# Power_management.net
KiCad netlist of a schematic drawn in Altium Designer
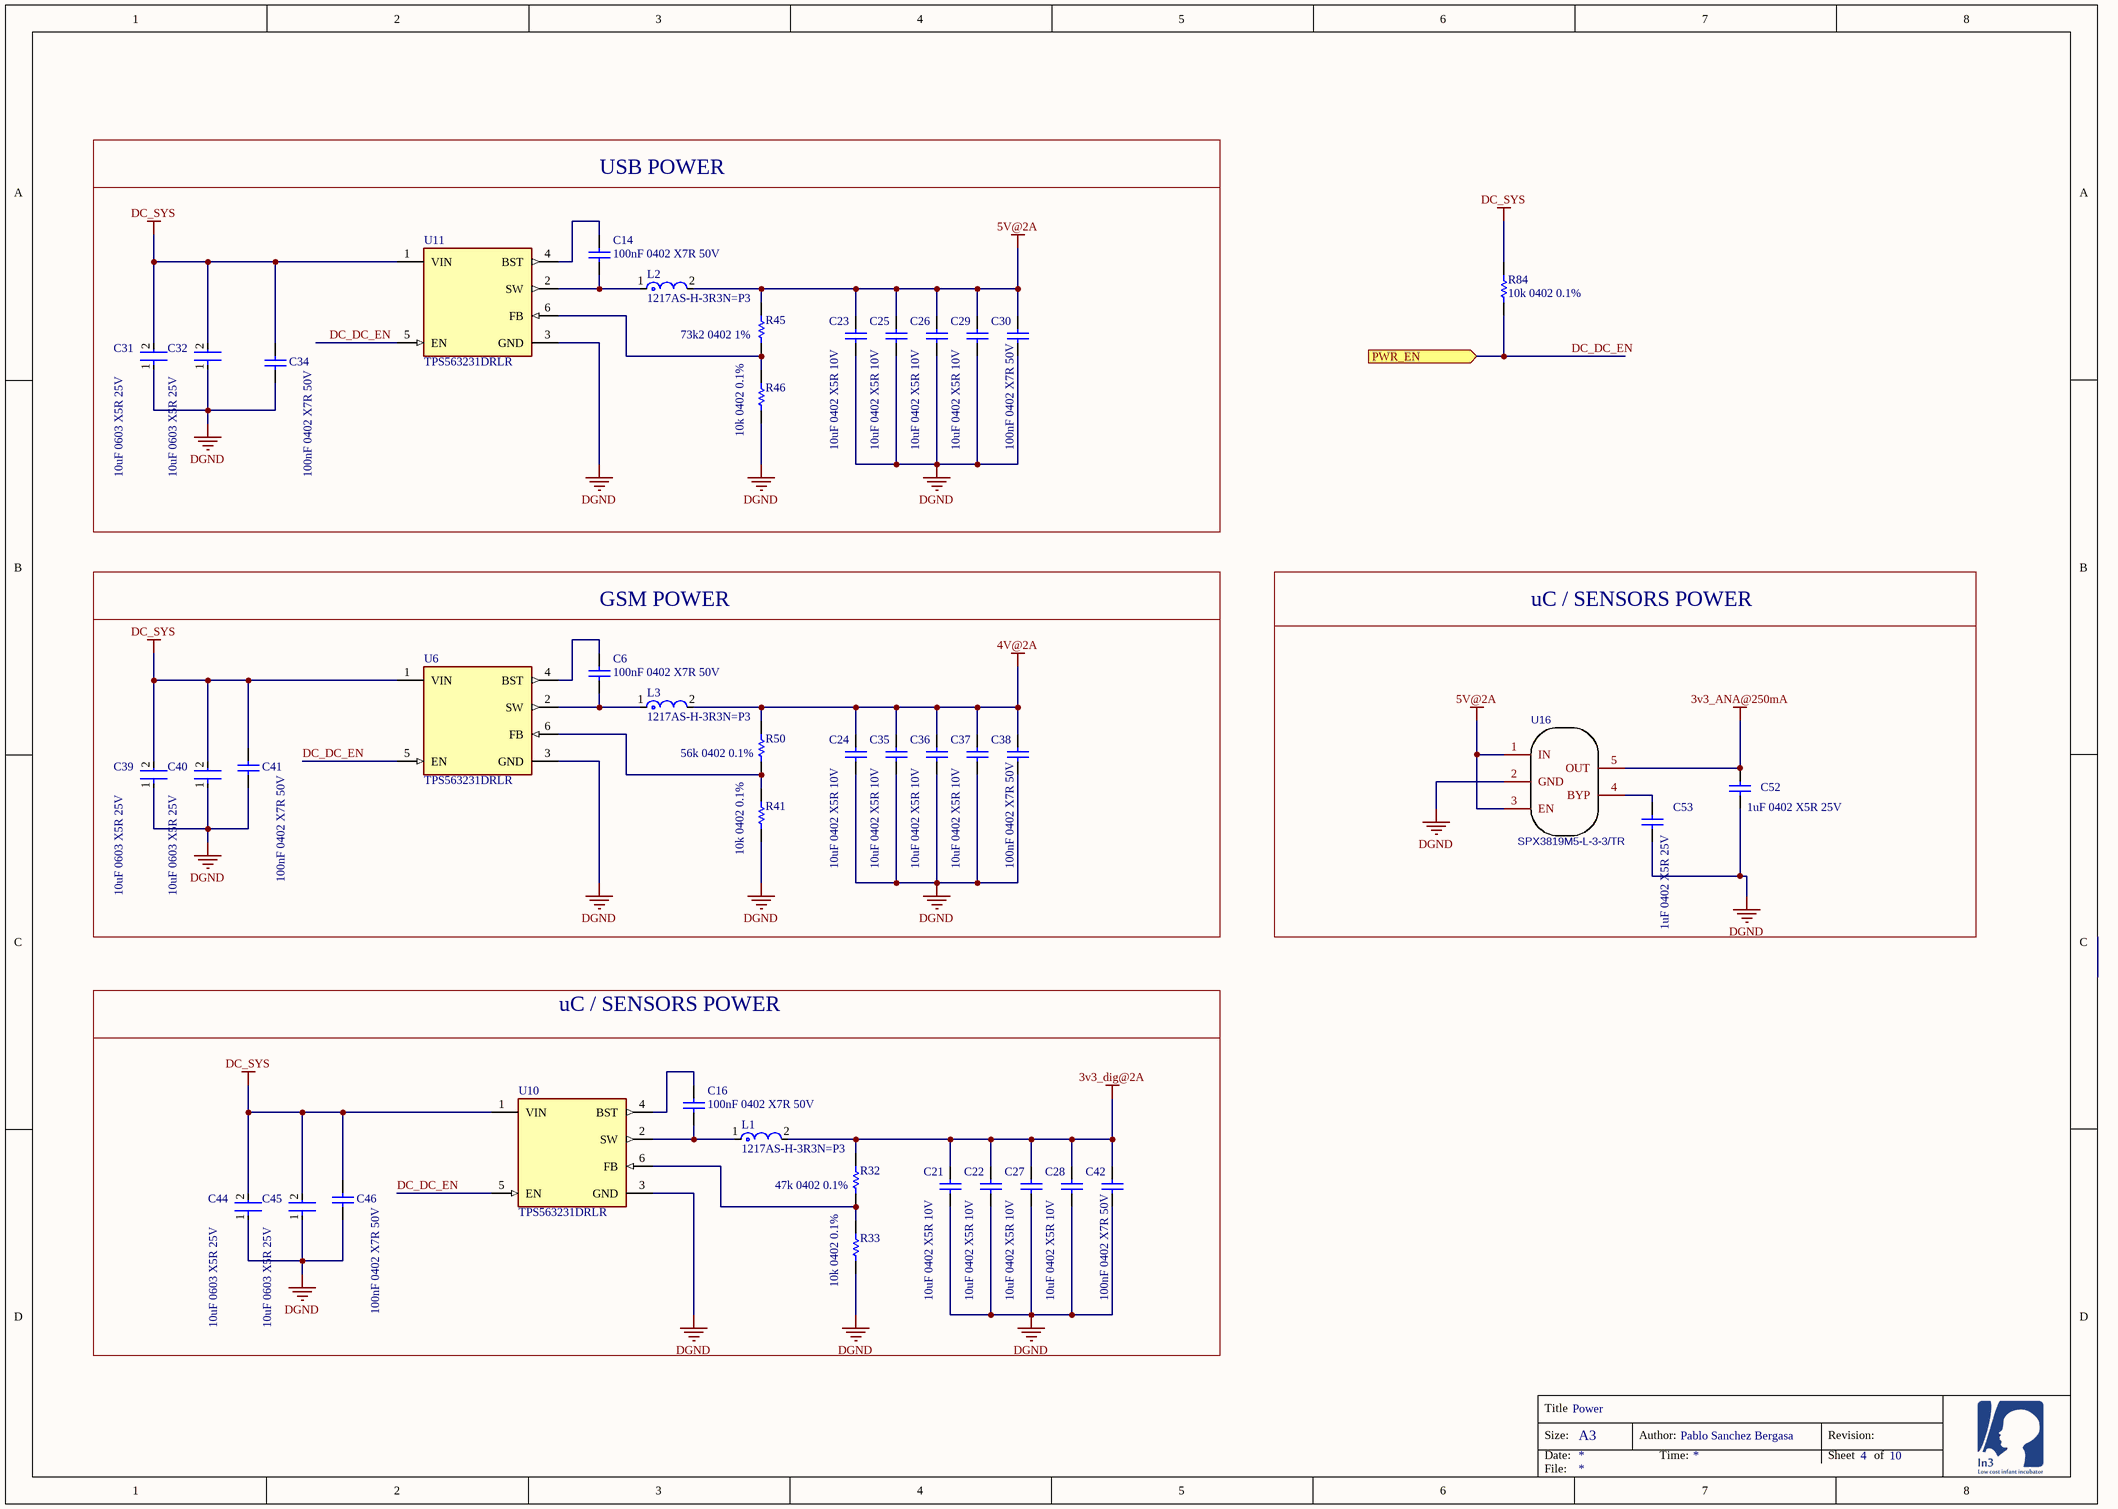
[diagram p0: Power_management.SchDoc]

(export (version "E")
  (design (tool "Eeschema 10.0.6"))
  (components
    (comp (ref "C6")
      (value "100nF 0402 X7R 50V")
      (footprint "CAPC1005X55X25NL5T10")
      (libsource (lib "Altium Content Vault") (part "CAP-NP-2"))
    )
    (comp (ref "C14")
      (value "100nF 0402 X7R 50V")
      (footprint "CAPC1005X55X25NL5T10")
      (libsource (lib "Altium Content Vault") (part "CAP-NP-2"))
    )
    (comp (ref "C16")
      (value "100nF 0402 X7R 50V")
      (footprint "CAPC1005X55X25NL5T10")
      (libsource (lib "Altium Content Vault") (part "CAP-NP-2"))
    )
    (comp (ref "C21")
      (value "10uF 0402 X5R 10V")
      (footprint "CAPC1005X55X25NL5T10")
      (libsource (lib "Altium Content Vault") (part "CAP-NP-2"))
    )
    (comp (ref "C22")
      (value "10uF 0402 X5R 10V")
      (footprint "CAPC1005X55X25NL5T10")
      (libsource (lib "Altium Content Vault") (part "CAP-NP-2"))
    )
    (comp (ref "C23")
      (value "10uF 0402 X5R 10V")
      (footprint "CAPC1005X55X25NL5T10")
      (libsource (lib "Altium Content Vault") (part "CAP-NP-2"))
    )
    (comp (ref "C24")
      (value "10uF 0402 X5R 10V")
      (footprint "CAPC1005X55X25NL5T10")
      (libsource (lib "Altium Content Vault") (part "CAP-NP-2"))
    )
    (comp (ref "C25")
      (value "10uF 0402 X5R 10V")
      (footprint "CAPC1005X55X25NL5T10")
      (libsource (lib "Altium Content Vault") (part "CAP-NP-2"))
    )
    (comp (ref "C26")
      (value "10uF 0402 X5R 10V")
      (footprint "CAPC1005X55X25NL5T10")
      (libsource (lib "Altium Content Vault") (part "CAP-NP-2"))
    )
    (comp (ref "C27")
      (value "10uF 0402 X5R 10V")
      (footprint "CAPC1005X55X25NL5T10")
      (libsource (lib "Altium Content Vault") (part "CAP-NP-2"))
    )
    (comp (ref "C28")
      (value "10uF 0402 X5R 10V")
      (footprint "CAPC1005X55X25NL5T10")
      (libsource (lib "Altium Content Vault") (part "CAP-NP-2"))
    )
    (comp (ref "C29")
      (value "10uF 0402 X5R 10V")
      (footprint "CAPC1005X55X25NL5T10")
      (libsource (lib "Altium Content Vault") (part "CAP-NP-2"))
    )
    (comp (ref "C30")
      (value "100nF 0402 X7R 50V")
      (footprint "CAPC1005X55X25NL5T10")
      (libsource (lib "Altium Content Vault") (part "CAP-NP-2"))
    )
    (comp (ref "C31")
      (value "10uF 0603 X5R 25V")
      (footprint "FP-GRM188-0_2-IPC_B")
      (libsource (lib "Altium Content Vault") (part "11868f565c42a9108669ba33697ecf6"))
    )
    (comp (ref "C32")
      (value "10uF 0603 X5R 25V")
      (footprint "FP-GRM188-0_2-IPC_B")
      (libsource (lib "Altium Content Vault") (part "11868f565c42a9108669ba33697ecf6"))
    )
    (comp (ref "C34")
      (value "100nF 0402 X7R 50V")
      (footprint "CAPC1005X55X25NL5T10")
      (libsource (lib "Altium Content Vault") (part "CAP-NP-2"))
    )
    (comp (ref "C35")
      (value "10uF 0402 X5R 10V")
      (footprint "CAPC1005X55X25NL5T10")
      (libsource (lib "Altium Content Vault") (part "CAP-NP-2"))
    )
    (comp (ref "C36")
      (value "10uF 0402 X5R 10V")
      (footprint "CAPC1005X55X25NL5T10")
      (libsource (lib "Altium Content Vault") (part "CAP-NP-2"))
    )
    (comp (ref "C37")
      (value "10uF 0402 X5R 10V")
      (footprint "CAPC1005X55X25NL5T10")
      (libsource (lib "Altium Content Vault") (part "CAP-NP-2"))
    )
    (comp (ref "C38")
      (value "100nF 0402 X7R 50V")
      (footprint "CAPC1005X55X25NL5T10")
      (libsource (lib "Altium Content Vault") (part "CAP-NP-2"))
    )
    (comp (ref "C39")
      (value "10uF 0603 X5R 25V")
      (footprint "FP-GRM188-0_2-IPC_B")
      (libsource (lib "Altium Content Vault") (part "11868f565c42a9108669ba33697ecf6"))
    )
    (comp (ref "C40")
      (value "10uF 0603 X5R 25V")
      (footprint "FP-GRM188-0_2-IPC_B")
      (libsource (lib "Altium Content Vault") (part "11868f565c42a9108669ba33697ecf6"))
    )
    (comp (ref "C41")
      (value "100nF 0402 X7R 50V")
      (footprint "CAPC1005X55X25NL5T10")
      (libsource (lib "Altium Content Vault") (part "CAP-NP-2"))
    )
    (comp (ref "C42")
      (value "100nF 0402 X7R 50V")
      (footprint "CAPC1005X55X25NL5T10")
      (libsource (lib "Altium Content Vault") (part "CAP-NP-2"))
    )
    (comp (ref "C44")
      (value "10uF 0603 X5R 25V")
      (footprint "FP-GRM188-0_2-IPC_B")
      (libsource (lib "Altium Content Vault") (part "11868f565c42a9108669ba33697ecf6"))
    )
    (comp (ref "C45")
      (value "10uF 0603 X5R 25V")
      (footprint "FP-GRM188-0_2-IPC_B")
      (libsource (lib "Altium Content Vault") (part "11868f565c42a9108669ba33697ecf6"))
    )
    (comp (ref "C46")
      (value "100nF 0402 X7R 50V")
      (footprint "CAPC1005X55X25NL5T10")
      (libsource (lib "Altium Content Vault") (part "CAP-NP-2"))
    )
    (comp (ref "C52")
      (value "1uF 0402 X5R 25V")
      (footprint "CAPC1005X55X25NL5T10")
      (libsource (lib "Altium Content Vault") (part "CAP-NP-2"))
    )
    (comp (ref "C53")
      (value "1uF 0402 X5R 25V")
      (footprint "CAPC1005X55X25NL5T10")
      (libsource (lib "Altium Content Vault") (part "CAP-NP-2"))
    )
    (comp (ref "L1")
      (value "1217AS-H-3R3N=P3")
      (footprint "FP-DEM8045C-MFG")
      (description "Shielded Wirewound Inductor 3.3uH 30% 6800mA 0.0144Ω SMD")
      (fields (field (name "TOLERANCE") "30%"))
      (libsource (lib "Altium Content Vault") (part "4cc4b267dca4c8e51f7102f422741d8"))
    )
    (comp (ref "L2")
      (value "1217AS-H-3R3N=P3")
      (footprint "FP-DEM8045C-MFG")
      (description "Shielded Wirewound Inductor 3.3uH 30% 6800mA 0.0144Ω SMD")
      (fields (field (name "TOLERANCE") "30%"))
      (libsource (lib "Altium Content Vault") (part "4cc4b267dca4c8e51f7102f422741d8"))
    )
    (comp (ref "L3")
      (value "1217AS-H-3R3N=P3")
      (footprint "FP-DEM8045C-MFG")
      (description "Shielded Wirewound Inductor 3.3uH 30% 6800mA 0.0144Ω SMD")
      (fields (field (name "TOLERANCE") "30%"))
      (libsource (lib "Altium Content Vault") (part "4cc4b267dca4c8e51f7102f422741d8"))
    )
    (comp (ref "R32")
      (value "47k 0402 0.1%")
      (footprint "RESC1005X40X25ML05T10")
      (libsource (lib "Altium Content Vault") (part "RES"))
    )
    (comp (ref "R33")
      (value "10k 0402 0.1%")
      (footprint "RESC1005X40X25ML05T10")
      (libsource (lib "Altium Content Vault") (part "RES"))
    )
    (comp (ref "R41")
      (value "10k 0402 0.1%")
      (footprint "RESC1005X40X25ML05T10")
      (libsource (lib "Altium Content Vault") (part "RES"))
    )
    (comp (ref "R45")
      (value "73k2 0402 1%")
      (footprint "RESC1005X40X25ML05T10")
      (fields (field (name "MANUFACTURER") "Yageo / Phycomp"))
      (libsource (lib "Altium Content Vault") (part "RES"))
    )
    (comp (ref "R46")
      (value "10k 0402 0.1%")
      (footprint "RESC1005X40X25ML05T10")
      (libsource (lib "Altium Content Vault") (part "RES"))
    )
    (comp (ref "R50")
      (value "56k 0402 0.1%")
      (footprint "RESC1005X40X25ML05T10")
      (libsource (lib "Altium Content Vault") (part "RES"))
    )
    (comp (ref "R84")
      (value "10k 0402 0.1%")
      (footprint "RESC1005X40X25ML05T10")
      (libsource (lib "Altium Content Vault") (part "RES"))
    )
    (comp (ref "U6")
      (value "TPS563231DRLR")
      (footprint "FP-DRL0006A-MFG")
      (description "POWER MANAGEMENT")
      (libsource (lib "Altium Content Vault") (part "4d860df4d3ea23b1aa54a495432cd8a"))
    )
    (comp (ref "U10")
      (value "TPS563231DRLR")
      (footprint "FP-DRL0006A-MFG")
      (description "POWER MANAGEMENT")
      (libsource (lib "Altium Content Vault") (part "4d860df4d3ea23b1aa54a495432cd8a"))
    )
    (comp (ref "U11")
      (value "TPS563231DRLR")
      (footprint "FP-DRL0006A-MFG")
      (description "POWER MANAGEMENT")
      (libsource (lib "Altium Content Vault") (part "4d860df4d3ea23b1aa54a495432cd8a"))
    )
    (comp (ref "U16")
      (value "SPX3819M5-L-3-3/TR")
      (footprint "SOT-23-5_L3.0-W1.7-P0.95-LS2.8-BR")
      (fields (field (name "BOM_SUPPLIER PART") "C9055"))
      (libsource (lib "LCSC") (part "SPX3819M5-L-3-3/TR"))
    )
  )
  (nets
    (net (code "1") (name "/DC_DC_EN") (class "Default")
      (node (ref "R84") (pin "2") (pinfunction "2_2") (pintype "passive"))
      (node (ref "U10") (pin "5") (pinfunction "EN_5") (pintype "input"))
      (node (ref "U11") (pin "5") (pinfunction "EN_5") (pintype "input"))
      (node (ref "U6") (pin "5") (pinfunction "EN_5") (pintype "input"))
    )
    (net (code "2") (name "3v3_ANA@250mA") (class "Default")
      (node (ref "C52") (pin "2") (pinfunction "2_2") (pintype "passive"))
      (node (ref "U16") (pin "5") (pinfunction "OUT_5") (pintype "passive"))
    )
    (net (code "3") (name "3v3_dig@2A") (class "Default")
      (node (ref "C21") (pin "2") (pinfunction "2_2") (pintype "passive"))
      (node (ref "C22") (pin "2") (pinfunction "2_2") (pintype "passive"))
      (node (ref "C27") (pin "2") (pinfunction "2_2") (pintype "passive"))
      (node (ref "C28") (pin "2") (pinfunction "2_2") (pintype "passive"))
      (node (ref "C42") (pin "2") (pinfunction "2_2") (pintype "passive"))
      (node (ref "L1") (pin "2") (pinfunction "2_2") (pintype "passive"))
      (node (ref "R32") (pin "2") (pinfunction "2_2") (pintype "passive"))
    )
    (net (code "4") (name "4V@2A") (class "Default")
      (node (ref "C24") (pin "2") (pinfunction "2_2") (pintype "passive"))
      (node (ref "C35") (pin "2") (pinfunction "2_2") (pintype "passive"))
      (node (ref "C36") (pin "2") (pinfunction "2_2") (pintype "passive"))
      (node (ref "C37") (pin "2") (pinfunction "2_2") (pintype "passive"))
      (node (ref "C38") (pin "2") (pinfunction "2_2") (pintype "passive"))
      (node (ref "L3") (pin "2") (pinfunction "2_2") (pintype "passive"))
      (node (ref "R50") (pin "2") (pinfunction "2_2") (pintype "passive"))
    )
    (net (code "5") (name "5V@2A") (class "Default")
      (node (ref "C23") (pin "2") (pinfunction "2_2") (pintype "passive"))
      (node (ref "C25") (pin "2") (pinfunction "2_2") (pintype "passive"))
      (node (ref "C26") (pin "2") (pinfunction "2_2") (pintype "passive"))
      (node (ref "C29") (pin "2") (pinfunction "2_2") (pintype "passive"))
      (node (ref "C30") (pin "2") (pinfunction "2_2") (pintype "passive"))
      (node (ref "L2") (pin "2") (pinfunction "2_2") (pintype "passive"))
      (node (ref "R45") (pin "2") (pinfunction "2_2") (pintype "passive"))
      (node (ref "U16") (pin "1") (pinfunction "IN_1") (pintype "passive"))
      (node (ref "U16") (pin "3") (pinfunction "EN_3") (pintype "passive"))
    )
    (net (code "6") (name "DC_SYS") (class "Default")
      (node (ref "C31") (pin "2") (pinfunction "2_2") (pintype "passive"))
      (node (ref "C32") (pin "2") (pinfunction "2_2") (pintype "passive"))
      (node (ref "C34") (pin "2") (pinfunction "2_2") (pintype "passive"))
      (node (ref "C39") (pin "2") (pinfunction "2_2") (pintype "passive"))
      (node (ref "C40") (pin "2") (pinfunction "2_2") (pintype "passive"))
      (node (ref "C41") (pin "2") (pinfunction "2_2") (pintype "passive"))
      (node (ref "C44") (pin "2") (pinfunction "2_2") (pintype "passive"))
      (node (ref "C45") (pin "2") (pinfunction "2_2") (pintype "passive"))
      (node (ref "C46") (pin "2") (pinfunction "2_2") (pintype "passive"))
      (node (ref "R84") (pin "1") (pinfunction "1_1") (pintype "passive"))
      (node (ref "U10") (pin "1") (pinfunction "VIN_1") (pintype "power_in"))
      (node (ref "U11") (pin "1") (pinfunction "VIN_1") (pintype "power_in"))
      (node (ref "U6") (pin "1") (pinfunction "VIN_1") (pintype "power_in"))
    )
    (net (code "7") (name "DGND") (class "Default")
      (node (ref "C21") (pin "1") (pinfunction "1_1") (pintype "passive"))
      (node (ref "C22") (pin "1") (pinfunction "1_1") (pintype "passive"))
      (node (ref "C23") (pin "1") (pinfunction "1_1") (pintype "passive"))
      (node (ref "C24") (pin "1") (pinfunction "1_1") (pintype "passive"))
      (node (ref "C25") (pin "1") (pinfunction "1_1") (pintype "passive"))
      (node (ref "C26") (pin "1") (pinfunction "1_1") (pintype "passive"))
      (node (ref "C27") (pin "1") (pinfunction "1_1") (pintype "passive"))
      (node (ref "C28") (pin "1") (pinfunction "1_1") (pintype "passive"))
      (node (ref "C29") (pin "1") (pinfunction "1_1") (pintype "passive"))
      (node (ref "C30") (pin "1") (pinfunction "1_1") (pintype "passive"))
      (node (ref "C31") (pin "1") (pinfunction "1_1") (pintype "passive"))
      (node (ref "C32") (pin "1") (pinfunction "1_1") (pintype "passive"))
      (node (ref "C34") (pin "1") (pinfunction "1_1") (pintype "passive"))
      (node (ref "C35") (pin "1") (pinfunction "1_1") (pintype "passive"))
      (node (ref "C36") (pin "1") (pinfunction "1_1") (pintype "passive"))
      (node (ref "C37") (pin "1") (pinfunction "1_1") (pintype "passive"))
      (node (ref "C38") (pin "1") (pinfunction "1_1") (pintype "passive"))
      (node (ref "C39") (pin "1") (pinfunction "1_1") (pintype "passive"))
      (node (ref "C40") (pin "1") (pinfunction "1_1") (pintype "passive"))
      (node (ref "C41") (pin "1") (pinfunction "1_1") (pintype "passive"))
      (node (ref "C42") (pin "1") (pinfunction "1_1") (pintype "passive"))
      (node (ref "C44") (pin "1") (pinfunction "1_1") (pintype "passive"))
      (node (ref "C45") (pin "1") (pinfunction "1_1") (pintype "passive"))
      (node (ref "C46") (pin "1") (pinfunction "1_1") (pintype "passive"))
      (node (ref "C52") (pin "1") (pinfunction "1_1") (pintype "passive"))
      (node (ref "C53") (pin "1") (pinfunction "1_1") (pintype "passive"))
      (node (ref "R33") (pin "1") (pinfunction "1_1") (pintype "passive"))
      (node (ref "R41") (pin "1") (pinfunction "1_1") (pintype "passive"))
      (node (ref "R46") (pin "1") (pinfunction "1_1") (pintype "passive"))
      (node (ref "U10") (pin "3") (pinfunction "GND_3") (pintype "power_in"))
      (node (ref "U11") (pin "3") (pinfunction "GND_3") (pintype "power_in"))
      (node (ref "U16") (pin "2") (pinfunction "GND_2") (pintype "passive"))
      (node (ref "U6") (pin "3") (pinfunction "GND_3") (pintype "power_in"))
    )
    (net (code "8") (name "Net-(U6-BST)") (class "Default")
      (node (ref "C6") (pin "2") (pinfunction "2_2") (pintype "passive"))
      (node (ref "U6") (pin "4") (pinfunction "BST_4") (pintype "output"))
    )
    (net (code "9") (name "Net-(U6-FB)") (class "Default")
      (node (ref "R41") (pin "2") (pinfunction "2_2") (pintype "passive"))
      (node (ref "R50") (pin "1") (pinfunction "1_1") (pintype "passive"))
      (node (ref "U6") (pin "6") (pinfunction "FB_6") (pintype "input"))
    )
    (net (code "10") (name "Net-(U6-SW)") (class "Default")
      (node (ref "C6") (pin "1") (pinfunction "1_1") (pintype "passive"))
      (node (ref "L3") (pin "1") (pinfunction "1_1") (pintype "passive"))
      (node (ref "U6") (pin "2") (pinfunction "SW_2") (pintype "output"))
    )
    (net (code "11") (name "Net-(U10-BST)") (class "Default")
      (node (ref "C16") (pin "2") (pinfunction "2_2") (pintype "passive"))
      (node (ref "U10") (pin "4") (pinfunction "BST_4") (pintype "output"))
    )
    (net (code "12") (name "Net-(U10-FB)") (class "Default")
      (node (ref "R32") (pin "1") (pinfunction "1_1") (pintype "passive"))
      (node (ref "R33") (pin "2") (pinfunction "2_2") (pintype "passive"))
      (node (ref "U10") (pin "6") (pinfunction "FB_6") (pintype "input"))
    )
    (net (code "13") (name "Net-(U10-SW)") (class "Default")
      (node (ref "C16") (pin "1") (pinfunction "1_1") (pintype "passive"))
      (node (ref "L1") (pin "1") (pinfunction "1_1") (pintype "passive"))
      (node (ref "U10") (pin "2") (pinfunction "SW_2") (pintype "output"))
    )
    (net (code "14") (name "Net-(U11-BST)") (class "Default")
      (node (ref "C14") (pin "2") (pinfunction "2_2") (pintype "passive"))
      (node (ref "U11") (pin "4") (pinfunction "BST_4") (pintype "output"))
    )
    (net (code "15") (name "Net-(U11-FB)") (class "Default")
      (node (ref "R45") (pin "1") (pinfunction "1_1") (pintype "passive"))
      (node (ref "R46") (pin "2") (pinfunction "2_2") (pintype "passive"))
      (node (ref "U11") (pin "6") (pinfunction "FB_6") (pintype "input"))
    )
    (net (code "16") (name "Net-(U11-SW)") (class "Default")
      (node (ref "C14") (pin "1") (pinfunction "1_1") (pintype "passive"))
      (node (ref "L2") (pin "1") (pinfunction "1_1") (pintype "passive"))
      (node (ref "U11") (pin "2") (pinfunction "SW_2") (pintype "output"))
    )
    (net (code "17") (name "Net-(U16-BYP)") (class "Default")
      (node (ref "C53") (pin "2") (pinfunction "2_2") (pintype "passive"))
      (node (ref "U16") (pin "4") (pinfunction "BYP_4") (pintype "passive"))
    )
  )
)
